# Franzininho.net
KiCad netlist of a schematic drawn in EAGLE
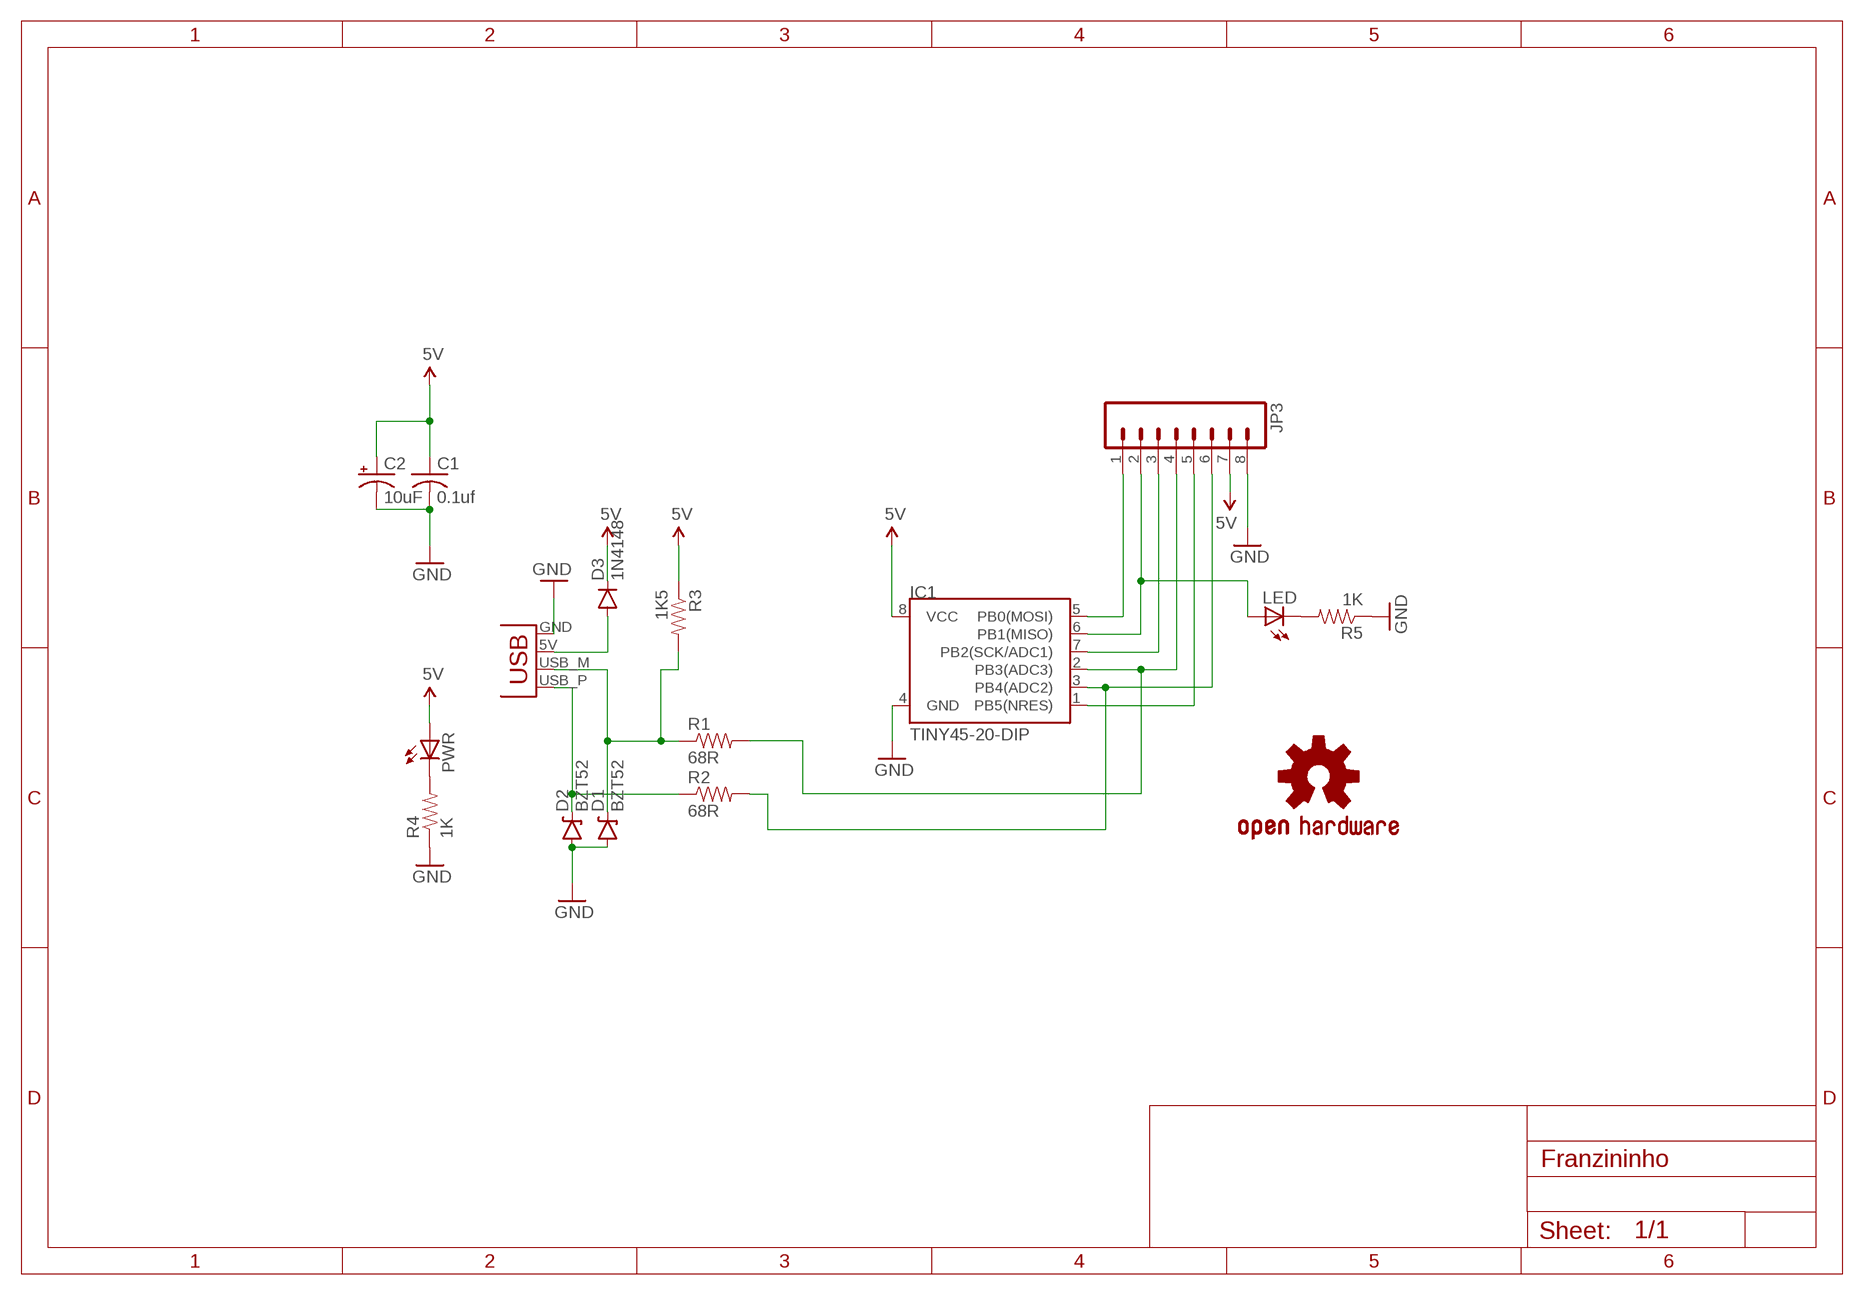
[diagram p0: schematic, sheet 1]

(export (version "E")
  (design (tool "Eeschema 10.0.6"))
  (components
    (comp (ref "C1")
      (value "0.1uf")
      (footprint "eagle-import:C025-025X050")
      (libsource (lib "eagle-import") (part "C-US025-025X050"))
    )
    (comp (ref "C2")
      (value "10uF")
      (footprint "eagle-import:E2,5-6E")
      (libsource (lib "eagle-import") (part "CPOL-USE2,5-6E"))
    )
    (comp (ref "D1")
      (value "BZT52")
      (footprint "eagle-import:DIODE-BZT52")
      (libsource (lib "eagle-import") (part "DIODE-ZENER"))
    )
    (comp (ref "D2")
      (value "BZT52")
      (footprint "eagle-import:DIODE-BZT52")
      (libsource (lib "eagle-import") (part "DIODE-ZENER"))
    )
    (comp (ref "D3")
      (value "1N4148")
      (footprint "eagle-import:DIODE-1N4148")
      (libsource (lib "eagle-import") (part "DIODE1N4148"))
    )
    (comp (ref "IC1")
      (value "TINY45-20-DIP")
      (footprint "eagle-import:DIP08")
      (libsource (lib "eagle-import") (part "ATTINY45TINY45-20-DIP"))
    )
    (comp (ref "JP3")
      (value "M08")
      (footprint "eagle-import:1X08_ROUND")
      (libsource (lib "eagle-import") (part "M08"))
    )
    (comp (ref "LED")
      (value "LED3MM")
      (footprint "eagle-import:LED3MM")
      (libsource (lib "eagle-import") (part "LED3MM"))
    )
    (comp (ref "LOGO1")
      (value "OSHW-LOGOL")
      (footprint "eagle-import:OSHW-LOGO-L")
      (libsource (lib "eagle-import") (part "OSHW-LOGOL"))
    )
    (comp (ref "PWR")
      (value "LED3MM")
      (footprint "eagle-import:LED3MM")
      (libsource (lib "eagle-import") (part "LED3MM"))
    )
    (comp (ref "R1")
      (value "68R")
      (footprint "eagle-import:AXIAL-0.4")
      (libsource (lib "eagle-import") (part "RESISTORPTH-1/4W"))
    )
    (comp (ref "R2")
      (value "68R")
      (footprint "eagle-import:AXIAL-0.4")
      (libsource (lib "eagle-import") (part "RESISTORPTH-1/4W"))
    )
    (comp (ref "R3")
      (value "1K5")
      (footprint "eagle-import:AXIAL-0.4")
      (libsource (lib "eagle-import") (part "RESISTORPTH-1/4W"))
    )
    (comp (ref "R4")
      (value "1K")
      (footprint "eagle-import:AXIAL-0.4")
      (libsource (lib "eagle-import") (part "RESISTORPTH-1/4W"))
    )
    (comp (ref "R5")
      (value "1K")
      (footprint "eagle-import:AXIAL-0.4")
      (libsource (lib "eagle-import") (part "RESISTORPTH-1/4W"))
    )
    (comp (ref "X1")
      (value "USBPCB")
      (footprint "eagle-import:USB-A-PCB")
      (libsource (lib "eagle-import") (part "USBPCB"))
    )
  )
  (nets
    (net (code "1") (name "5V") (class "Default")
      (node (ref "C1") (pin "1") (pinfunction "1_1") (pintype "passive"))
      (node (ref "C2") (pin "+") (pinfunction "+_+") (pintype "passive"))
      (node (ref "D3") (pin "C") (pinfunction "C_C") (pintype "passive"))
      (node (ref "IC1") (pin "8") (pinfunction "VCC_8") (pintype "bidirectional"))
      (node (ref "JP3") (pin "7") (pinfunction "7_7") (pintype "passive"))
      (node (ref "PWR") (pin "A") (pinfunction "A_A") (pintype "passive"))
      (node (ref "R3") (pin "P$1") (pinfunction "1_P$1") (pintype "passive"))
    )
    (net (code "2") (name "GND") (class "Default")
      (node (ref "C1") (pin "2") (pinfunction "2_2") (pintype "passive"))
      (node (ref "C2") (pin "-") (pinfunction "-_-") (pintype "passive"))
      (node (ref "D1") (pin "A") (pinfunction "A_A") (pintype "passive"))
      (node (ref "D2") (pin "A") (pinfunction "A_A") (pintype "passive"))
      (node (ref "IC1") (pin "4") (pinfunction "GND_4") (pintype "bidirectional"))
      (node (ref "JP3") (pin "8") (pinfunction "8_8") (pintype "passive"))
      (node (ref "R4") (pin "P$1") (pinfunction "1_P$1") (pintype "passive"))
      (node (ref "R5") (pin "P$1") (pinfunction "1_P$1") (pintype "passive"))
      (node (ref "X1") (pin "GND") (pinfunction "GND_GND") (pintype "bidirectional"))
    )
    (net (code "3") (name "Net-(IC1-PB0(MOSI))") (class "Default")
      (node (ref "IC1") (pin "5") (pinfunction "PB0(MOSI)_5") (pintype "bidirectional"))
      (node (ref "JP3") (pin "1") (pinfunction "1_1") (pintype "passive"))
    )
    (net (code "4") (name "Net-(IC1-PB1(MISO))") (class "Default")
      (node (ref "IC1") (pin "6") (pinfunction "PB1(MISO)_6") (pintype "bidirectional"))
      (node (ref "JP3") (pin "2") (pinfunction "2_2") (pintype "passive"))
      (node (ref "LED") (pin "A") (pinfunction "A_A") (pintype "passive"))
    )
    (net (code "5") (name "Net-(IC1-PB2(SCK{slash}ADC1))") (class "Default")
      (node (ref "IC1") (pin "7") (pinfunction "PB2(SCK/ADC1)_7") (pintype "bidirectional"))
      (node (ref "JP3") (pin "3") (pinfunction "3_3") (pintype "passive"))
    )
    (net (code "6") (name "Net-(IC1-PB3(ADC3))") (class "Default")
      (node (ref "IC1") (pin "2") (pinfunction "PB3(ADC3)_2") (pintype "bidirectional"))
      (node (ref "JP3") (pin "4") (pinfunction "4_4") (pintype "passive"))
      (node (ref "R1") (pin "P$2") (pinfunction "2_P$2") (pintype "passive"))
    )
    (net (code "7") (name "Net-(IC1-PB4(ADC2))") (class "Default")
      (node (ref "IC1") (pin "3") (pinfunction "PB4(ADC2)_3") (pintype "bidirectional"))
      (node (ref "JP3") (pin "6") (pinfunction "6_6") (pintype "passive"))
      (node (ref "R2") (pin "P$2") (pinfunction "2_P$2") (pintype "passive"))
    )
    (net (code "8") (name "Net-(IC1-PB5(NRES))") (class "Default")
      (node (ref "IC1") (pin "1") (pinfunction "PB5(NRES)_1") (pintype "bidirectional"))
      (node (ref "JP3") (pin "5") (pinfunction "5_5") (pintype "passive"))
    )
    (net (code "9") (name "Net-(LED-C)") (class "Default")
      (node (ref "LED") (pin "K") (pinfunction "C_K") (pintype "passive"))
      (node (ref "R5") (pin "P$2") (pinfunction "2_P$2") (pintype "passive"))
    )
    (net (code "10") (name "Net-(PWR-C)") (class "Default")
      (node (ref "PWR") (pin "K") (pinfunction "C_K") (pintype "passive"))
      (node (ref "R4") (pin "P$2") (pinfunction "2_P$2") (pintype "passive"))
    )
    (net (code "11") (name "Net-(R1-1)") (class "Default")
      (node (ref "D1") (pin "C") (pinfunction "C_C") (pintype "passive"))
      (node (ref "R1") (pin "P$1") (pinfunction "1_P$1") (pintype "passive"))
      (node (ref "R3") (pin "P$2") (pinfunction "2_P$2") (pintype "passive"))
      (node (ref "X1") (pin "USB_M") (pinfunction "D-_USB_M") (pintype "bidirectional"))
    )
    (net (code "12") (name "Net-(R2-1)") (class "Default")
      (node (ref "D2") (pin "C") (pinfunction "C_C") (pintype "passive"))
      (node (ref "R2") (pin "P$1") (pinfunction "1_P$1") (pintype "passive"))
      (node (ref "X1") (pin "USB_P") (pinfunction "D+_USB_P") (pintype "bidirectional"))
    )
    (net (code "13") (name "Net-(X1-VBUS)") (class "Default")
      (node (ref "D3") (pin "A") (pinfunction "A_A") (pintype "passive"))
      (node (ref "X1") (pin "5V") (pinfunction "VBUS_5V") (pintype "bidirectional"))
    )
  )
)
